# zumo_lb_01.net
KiCad netlist of a schematic drawn in EAGLE
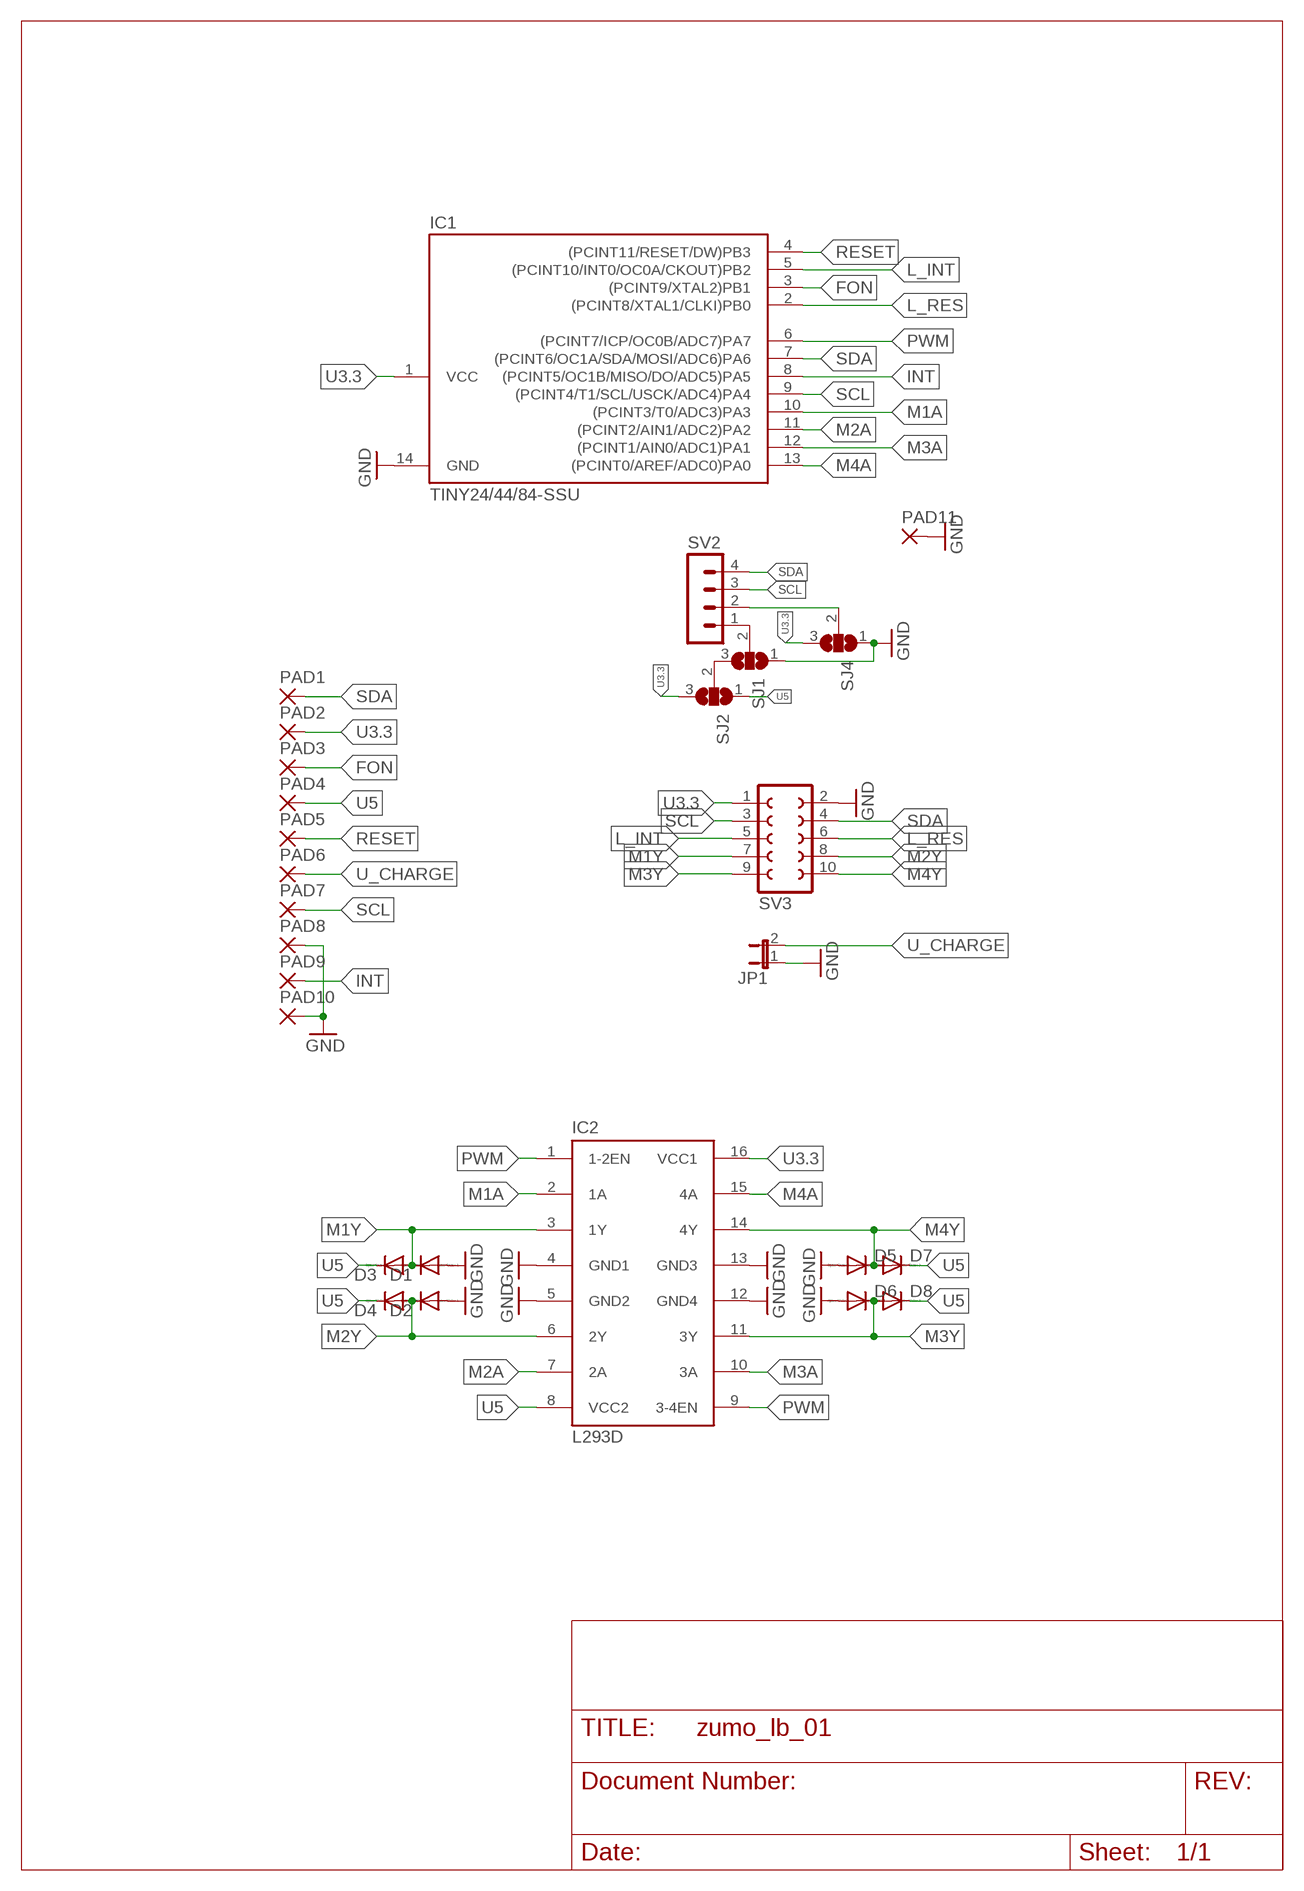
[diagram p0: schematic, sheet 1]

(export (version "E")
  (design (tool "Eeschema 10.0.6"))
  (components
    (comp (ref "D1")
      (value "DIODE-MINIMELF")
      (footprint "eagle-import:MINIMELF")
      (libsource (lib "eagle-import") (part "DIODE-MINIMELF"))
    )
    (comp (ref "D2")
      (value "DIODE-MINIMELF")
      (footprint "eagle-import:MINIMELF")
      (libsource (lib "eagle-import") (part "DIODE-MINIMELF"))
    )
    (comp (ref "D3")
      (value "DIODE-MINIMELF")
      (footprint "eagle-import:MINIMELF")
      (libsource (lib "eagle-import") (part "DIODE-MINIMELF"))
    )
    (comp (ref "D4")
      (value "DIODE-MINIMELF")
      (footprint "eagle-import:MINIMELF")
      (libsource (lib "eagle-import") (part "DIODE-MINIMELF"))
    )
    (comp (ref "D5")
      (value "DIODE-MINIMELF")
      (footprint "eagle-import:MINIMELF")
      (libsource (lib "eagle-import") (part "DIODE-MINIMELF"))
    )
    (comp (ref "D6")
      (value "DIODE-MINIMELF")
      (footprint "eagle-import:MINIMELF")
      (libsource (lib "eagle-import") (part "DIODE-MINIMELF"))
    )
    (comp (ref "D7")
      (value "DIODE-MINIMELF")
      (footprint "eagle-import:MINIMELF")
      (libsource (lib "eagle-import") (part "DIODE-MINIMELF"))
    )
    (comp (ref "D8")
      (value "DIODE-MINIMELF")
      (footprint "eagle-import:MINIMELF")
      (libsource (lib "eagle-import") (part "DIODE-MINIMELF"))
    )
    (comp (ref "IC1")
      (value "TINY24/44/84-SSU")
      (footprint "eagle-import:SOIC14")
      (libsource (lib "eagle-import") (part "TINY24/44/84-SSU"))
    )
    (comp (ref "IC2")
      (value "L293D")
      (footprint "eagle-import:DIL16")
      (libsource (lib "eagle-import") (part "L293D"))
    )
    (comp (ref "JP1")
      (value "JP1E")
      (footprint "eagle-import:JP1")
      (libsource (lib "eagle-import") (part "JP1E"))
    )
    (comp (ref "PAD1")
      (value "SMD2")
      (footprint "eagle-import:SMD1,27-2,54")
      (libsource (lib "eagle-import") (part "SMD2"))
    )
    (comp (ref "PAD2")
      (value "SMD2")
      (footprint "eagle-import:SMD1,27-2,54")
      (libsource (lib "eagle-import") (part "SMD2"))
    )
    (comp (ref "PAD3")
      (value "SMD2")
      (footprint "eagle-import:SMD1,27-2,54")
      (libsource (lib "eagle-import") (part "SMD2"))
    )
    (comp (ref "PAD4")
      (value "SMD2")
      (footprint "eagle-import:SMD1,27-2,54")
      (libsource (lib "eagle-import") (part "SMD2"))
    )
    (comp (ref "PAD5")
      (value "SMD2")
      (footprint "eagle-import:SMD1,27-2,54")
      (libsource (lib "eagle-import") (part "SMD2"))
    )
    (comp (ref "PAD6")
      (value "SMD2")
      (footprint "eagle-import:SMD1,27-2,54")
      (libsource (lib "eagle-import") (part "SMD2"))
    )
    (comp (ref "PAD7")
      (value "SMD2")
      (footprint "eagle-import:SMD1,27-2,54")
      (libsource (lib "eagle-import") (part "SMD2"))
    )
    (comp (ref "PAD8")
      (value "SMD2")
      (footprint "eagle-import:SMD1,27-2,54")
      (libsource (lib "eagle-import") (part "SMD2"))
    )
    (comp (ref "PAD9")
      (value "SMD2")
      (footprint "eagle-import:SMD1,27-2,54")
      (libsource (lib "eagle-import") (part "SMD2"))
    )
    (comp (ref "PAD10")
      (value "SMD2")
      (footprint "eagle-import:SMD1,27-2,54")
      (libsource (lib "eagle-import") (part "SMD2"))
    )
    (comp (ref "PAD11")
      (value "3,81/1,4")
      (footprint "eagle-import:3,81_1,4")
      (libsource (lib "eagle-import") (part "3,81/1,4"))
    )
    (comp (ref "SJ1")
      (value "SJ2W")
      (footprint "eagle-import:SJ_2")
      (libsource (lib "eagle-import") (part "SJ2W"))
    )
    (comp (ref "SJ2")
      (value "SJ2W")
      (footprint "eagle-import:SJ_2")
      (libsource (lib "eagle-import") (part "SJ2W"))
    )
    (comp (ref "SJ4")
      (value "SJ2W")
      (footprint "eagle-import:SJ_2")
      (libsource (lib "eagle-import") (part "SJ2W"))
    )
    (comp (ref "SV2")
      (value "MA04-1")
      (footprint "eagle-import:MA04-1")
      (libsource (lib "eagle-import") (part "MA04-1"))
    )
    (comp (ref "SV3")
      (value "FE05-2")
      (footprint "eagle-import:FE05-2")
      (libsource (lib "eagle-import") (part "FE05-2"))
    )
  )
  (nets
    (net (code "1") (name "FON") (class "Default")
      (node (ref "IC1") (pin "3") (pinfunction "(PCINT9/XTAL2)PB1_3") (pintype "bidirectional"))
      (node (ref "PAD3") (pin "1") (pinfunction "P_1") (pintype "passive"))
    )
    (net (code "2") (name "GND") (class "Default")
      (node (ref "D1") (pin "A") (pinfunction "A_A") (pintype "passive"))
      (node (ref "D2") (pin "A") (pinfunction "A_A") (pintype "passive"))
      (node (ref "D5") (pin "A") (pinfunction "A_A") (pintype "passive"))
      (node (ref "D6") (pin "A") (pinfunction "A_A") (pintype "passive"))
      (node (ref "IC1") (pin "14") (pinfunction "GND_14") (pintype "power_in"))
      (node (ref "IC2") (pin "12") (pinfunction "GND4_12") (pintype "power_in"))
      (node (ref "IC2") (pin "13") (pinfunction "GND3_13") (pintype "power_in"))
      (node (ref "IC2") (pin "4") (pinfunction "GND1_4") (pintype "power_in"))
      (node (ref "IC2") (pin "5") (pinfunction "GND2_5") (pintype "power_in"))
      (node (ref "JP1") (pin "1") (pinfunction "1_1") (pintype "passive"))
      (node (ref "PAD10") (pin "1") (pinfunction "P_1") (pintype "passive"))
      (node (ref "PAD11") (pin "1") (pinfunction "P_1") (pintype "passive"))
      (node (ref "PAD8") (pin "1") (pinfunction "P_1") (pintype "passive"))
      (node (ref "SJ1") (pin "1") (pinfunction "1_1") (pintype "passive"))
      (node (ref "SJ4") (pin "1") (pinfunction "1_1") (pintype "passive"))
      (node (ref "SV3") (pin "2") (pinfunction "2_2") (pintype "passive"))
    )
    (net (code "3") (name "INT") (class "Default")
      (node (ref "IC1") (pin "8") (pinfunction "(PCINT5/OC1B/MISO/DO/ADC5)PA5_8") (pintype "bidirectional"))
      (node (ref "PAD9") (pin "1") (pinfunction "P_1") (pintype "passive"))
    )
    (net (code "4") (name "L_INT") (class "Default")
      (node (ref "IC1") (pin "5") (pinfunction "(PCINT10/INT0/OC0A/CKOUT)PB2_5") (pintype "bidirectional"))
      (node (ref "SV3") (pin "5") (pinfunction "5_5") (pintype "passive"))
    )
    (net (code "5") (name "L_RES") (class "Default")
      (node (ref "IC1") (pin "2") (pinfunction "(PCINT8/XTAL1/CLKI)PB0_2") (pintype "bidirectional"))
      (node (ref "SV3") (pin "6") (pinfunction "6_6") (pintype "passive"))
    )
    (net (code "6") (name "M1A") (class "Default")
      (node (ref "IC1") (pin "10") (pinfunction "(PCINT3/T0/ADC3)PA3_10") (pintype "bidirectional"))
      (node (ref "IC2") (pin "2") (pinfunction "1A_2") (pintype "input"))
    )
    (net (code "7") (name "M1Y") (class "Default")
      (node (ref "D1") (pin "C") (pinfunction "C_C") (pintype "passive"))
      (node (ref "D3") (pin "A") (pinfunction "A_A") (pintype "passive"))
      (node (ref "IC2") (pin "3") (pinfunction "1Y_3") (pintype "output"))
      (node (ref "SV3") (pin "7") (pinfunction "7_7") (pintype "passive"))
    )
    (net (code "8") (name "M2A") (class "Default")
      (node (ref "IC1") (pin "11") (pinfunction "(PCINT2/AIN1/ADC2)PA2_11") (pintype "bidirectional"))
      (node (ref "IC2") (pin "7") (pinfunction "2A_7") (pintype "input"))
    )
    (net (code "9") (name "M2Y") (class "Default")
      (node (ref "D2") (pin "C") (pinfunction "C_C") (pintype "passive"))
      (node (ref "D4") (pin "A") (pinfunction "A_A") (pintype "passive"))
      (node (ref "IC2") (pin "6") (pinfunction "2Y_6") (pintype "output"))
      (node (ref "SV3") (pin "8") (pinfunction "8_8") (pintype "passive"))
    )
    (net (code "10") (name "M3A") (class "Default")
      (node (ref "IC1") (pin "12") (pinfunction "(PCINT1/AIN0/ADC1)PA1_12") (pintype "bidirectional"))
      (node (ref "IC2") (pin "10") (pinfunction "3A_10") (pintype "input"))
    )
    (net (code "11") (name "M3Y") (class "Default")
      (node (ref "D6") (pin "C") (pinfunction "C_C") (pintype "passive"))
      (node (ref "D8") (pin "A") (pinfunction "A_A") (pintype "passive"))
      (node (ref "IC2") (pin "11") (pinfunction "3Y_11") (pintype "output"))
      (node (ref "SV3") (pin "9") (pinfunction "9_9") (pintype "passive"))
    )
    (net (code "12") (name "M4A") (class "Default")
      (node (ref "IC1") (pin "13") (pinfunction "(PCINT0/AREF/ADC0)PA0_13") (pintype "bidirectional"))
      (node (ref "IC2") (pin "15") (pinfunction "4A_15") (pintype "input"))
    )
    (net (code "13") (name "M4Y") (class "Default")
      (node (ref "D5") (pin "C") (pinfunction "C_C") (pintype "passive"))
      (node (ref "D7") (pin "A") (pinfunction "A_A") (pintype "passive"))
      (node (ref "IC2") (pin "14") (pinfunction "4Y_14") (pintype "output"))
      (node (ref "SV3") (pin "10") (pinfunction "10_10") (pintype "passive"))
    )
    (net (code "14") (name "Net-(SJ1-Pad2)") (class "Default")
      (node (ref "SJ1") (pin "2") (pinfunction "2_2") (pintype "passive"))
      (node (ref "SV2") (pin "1") (pinfunction "1_1") (pintype "passive"))
    )
    (net (code "15") (name "Net-(SJ1-Pad3)") (class "Default")
      (node (ref "SJ1") (pin "3") (pinfunction "3_3") (pintype "passive"))
      (node (ref "SJ2") (pin "2") (pinfunction "2_2") (pintype "passive"))
    )
    (net (code "16") (name "Net-(SJ4-Pad2)") (class "Default")
      (node (ref "SJ4") (pin "2") (pinfunction "2_2") (pintype "passive"))
      (node (ref "SV2") (pin "2") (pinfunction "2_2") (pintype "passive"))
    )
    (net (code "17") (name "PWM") (class "Default")
      (node (ref "IC1") (pin "6") (pinfunction "(PCINT7/ICP/OC0B/ADC7)PA7_6") (pintype "bidirectional"))
      (node (ref "IC2") (pin "1") (pinfunction "1-2EN_1") (pintype "input"))
      (node (ref "IC2") (pin "9") (pinfunction "3-4EN_9") (pintype "input"))
    )
    (net (code "18") (name "RESET") (class "Default")
      (node (ref "IC1") (pin "4") (pinfunction "(PCINT11/RESET/DW)PB3_4") (pintype "bidirectional"))
      (node (ref "PAD5") (pin "1") (pinfunction "P_1") (pintype "passive"))
    )
    (net (code "19") (name "SCL") (class "Default")
      (node (ref "IC1") (pin "9") (pinfunction "(PCINT4/T1/SCL/USCK/ADC4)PA4_9") (pintype "bidirectional"))
      (node (ref "PAD7") (pin "1") (pinfunction "P_1") (pintype "passive"))
      (node (ref "SV2") (pin "3") (pinfunction "3_3") (pintype "passive"))
      (node (ref "SV3") (pin "3") (pinfunction "3_3") (pintype "passive"))
    )
    (net (code "20") (name "SDA") (class "Default")
      (node (ref "IC1") (pin "7") (pinfunction "(PCINT6/OC1A/SDA/MOSI/ADC6)PA6_7") (pintype "bidirectional"))
      (node (ref "PAD1") (pin "1") (pinfunction "P_1") (pintype "passive"))
      (node (ref "SV2") (pin "4") (pinfunction "4_4") (pintype "passive"))
      (node (ref "SV3") (pin "4") (pinfunction "4_4") (pintype "passive"))
    )
    (net (code "21") (name "U3.3") (class "Default")
      (node (ref "IC1") (pin "1") (pinfunction "VCC_1") (pintype "power_in"))
      (node (ref "IC2") (pin "16") (pinfunction "VCC1_16") (pintype "power_in"))
      (node (ref "PAD2") (pin "1") (pinfunction "P_1") (pintype "passive"))
      (node (ref "SJ2") (pin "3") (pinfunction "3_3") (pintype "passive"))
      (node (ref "SJ4") (pin "3") (pinfunction "3_3") (pintype "passive"))
      (node (ref "SV3") (pin "1") (pinfunction "1_1") (pintype "passive"))
    )
    (net (code "22") (name "U5") (class "Default")
      (node (ref "D3") (pin "C") (pinfunction "C_C") (pintype "passive"))
      (node (ref "D4") (pin "C") (pinfunction "C_C") (pintype "passive"))
      (node (ref "D7") (pin "C") (pinfunction "C_C") (pintype "passive"))
      (node (ref "D8") (pin "C") (pinfunction "C_C") (pintype "passive"))
      (node (ref "IC2") (pin "8") (pinfunction "VCC2_8") (pintype "power_in"))
      (node (ref "PAD4") (pin "1") (pinfunction "P_1") (pintype "passive"))
      (node (ref "SJ2") (pin "1") (pinfunction "1_1") (pintype "passive"))
    )
    (net (code "23") (name "U_CHARGE") (class "Default")
      (node (ref "JP1") (pin "2") (pinfunction "2_2") (pintype "passive"))
      (node (ref "PAD6") (pin "1") (pinfunction "P_1") (pintype "passive"))
    )
  )
)
